# MCU103A_XDS110_MCU.net
KiCad netlist of a schematic drawn in Altium Designer
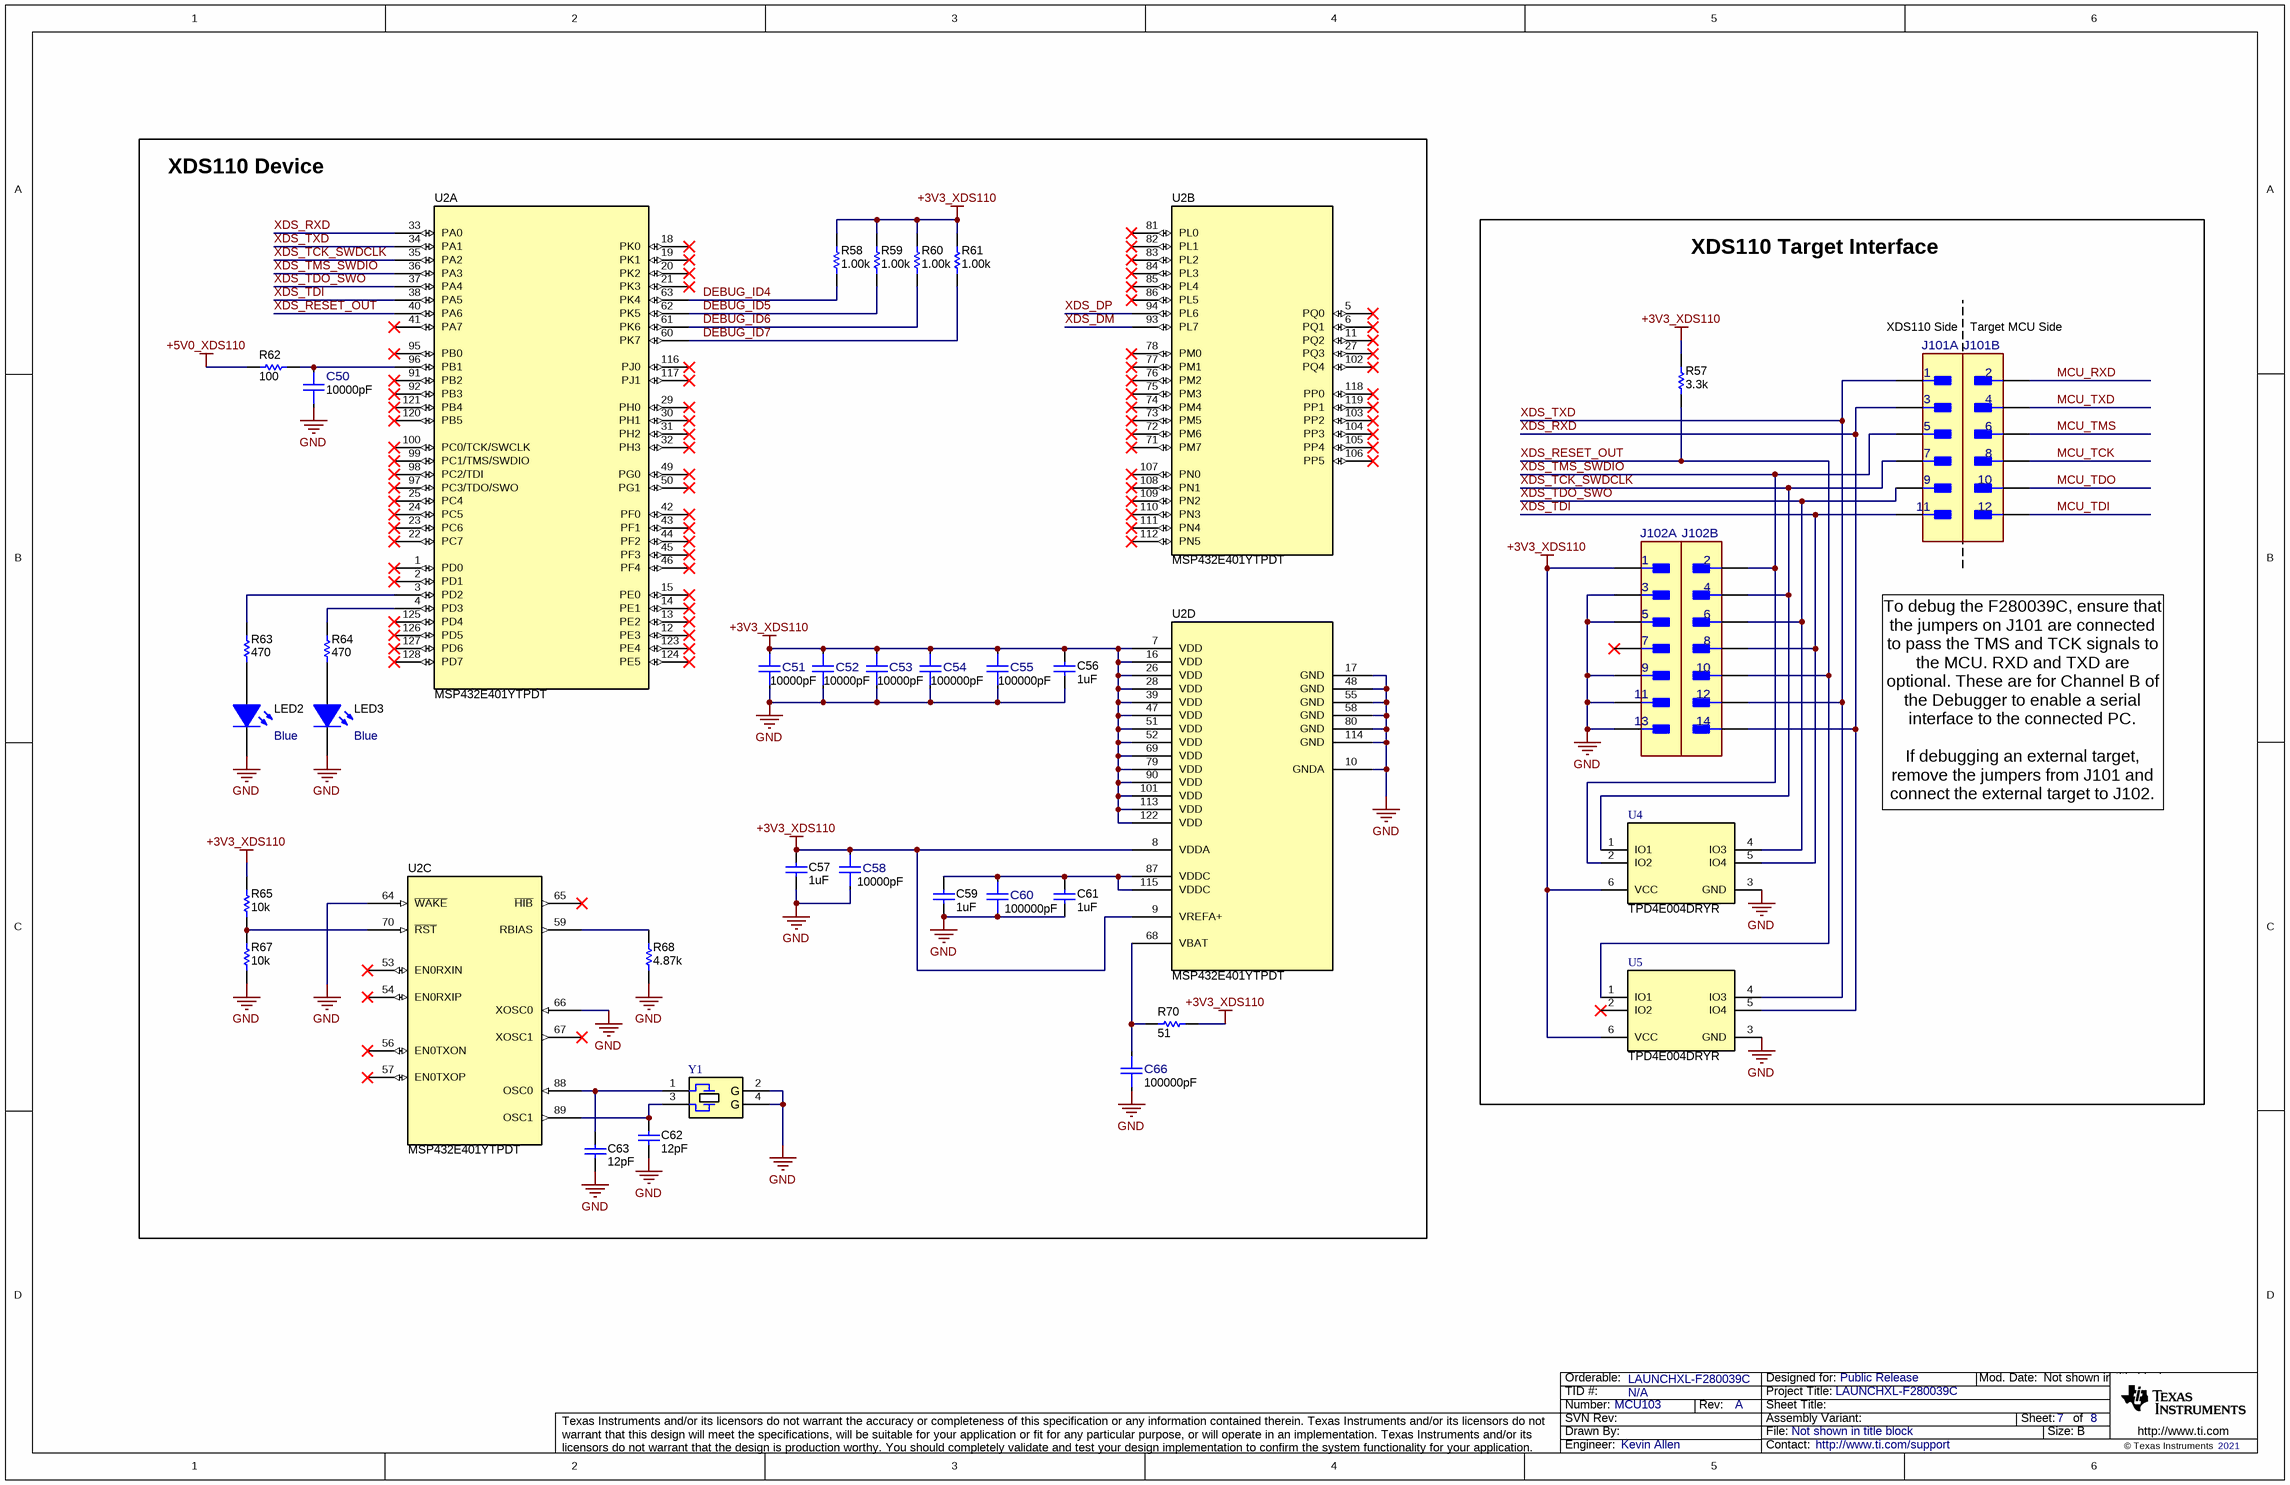
[diagram p0: MCU103A_XDS110_MCU.SchDoc]

(export (version "E")
  (design (tool "Eeschema 10.0.6"))
  (components
    (comp (ref "C50")
      (value "885012205050")
      (footprint "FP-885012205050_0402-MFG")
      (description "10000pF ±10% 25V Ceramic Capacitor X7R 0402 (1005 Metric)")
      (fields
        (field (name "MANUFACTURER") "Wurth Electronics")
        (field (name "VALUEDISPLAYED") "10000pF")
        (field (name "MOUSER PART NUMBER") "710-885012205050")
      )
      (libsource (lib "Altium Vault - TI") (part "SYM-885012205050"))
    )
    (comp (ref "C51")
      (value "885012205050")
      (footprint "FP-885012205050_0402-MFG")
      (description "10000pF ±10% 25V Ceramic Capacitor X7R 0402 (1005 Metric)")
      (fields
        (field (name "MANUFACTURER") "Wurth Electronics")
        (field (name "VALUEDISPLAYED") "10000pF")
        (field (name "MOUSER PART NUMBER") "710-885012205050")
      )
      (libsource (lib "Altium Vault - TI") (part "SYM-885012205050"))
    )
    (comp (ref "C52")
      (value "885012205050")
      (footprint "FP-885012205050_0402-MFG")
      (description "10000pF ±10% 25V Ceramic Capacitor X7R 0402 (1005 Metric)")
      (fields
        (field (name "MANUFACTURER") "Wurth Electronics")
        (field (name "VALUEDISPLAYED") "10000pF")
        (field (name "MOUSER PART NUMBER") "710-885012205050")
      )
      (libsource (lib "Altium Vault - TI") (part "SYM-885012205050"))
    )
    (comp (ref "C53")
      (value "885012205050")
      (footprint "FP-885012205050_0402-MFG")
      (description "10000pF ±10% 25V Ceramic Capacitor X7R 0402 (1005 Metric)")
      (fields
        (field (name "MANUFACTURER") "Wurth Electronics")
        (field (name "VALUEDISPLAYED") "10000pF")
        (field (name "MOUSER PART NUMBER") "710-885012205050")
      )
      (libsource (lib "Altium Vault - TI") (part "SYM-885012205050"))
    )
    (comp (ref "C54")
      (value "885012205018")
      (footprint "FP-885012205018_0402-MFG")
      (description "0.1µF ±10% 10V Ceramic Capacitor X7R 0402 (1005 Metric)")
      (fields
        (field (name "MANUFACTURER") "Wurth Electronics")
        (field (name "MOUSER PART NUMBER") "710-885012205018")
        (field (name "VALUEDISPLAYED") "100000pF")
      )
      (libsource (lib "Altium Vault - TI") (part "SYM-885012205018"))
    )
    (comp (ref "C55")
      (value "885012205018")
      (footprint "FP-885012205018_0402-MFG")
      (description "0.1µF ±10% 10V Ceramic Capacitor X7R 0402 (1005 Metric)")
      (fields
        (field (name "MANUFACTURER") "Wurth Electronics")
        (field (name "MOUSER PART NUMBER") "710-885012205018")
        (field (name "VALUEDISPLAYED") "100000pF")
      )
      (libsource (lib "Altium Vault - TI") (part "SYM-885012205018"))
    )
    (comp (ref "C56")
      (value "885012105012")
      (footprint "0402")
      (description "CAP, CERM, 1 uF, 10 V,+/- 20%, X5R, 0402")
      (fields
        (field (name "VALUEDISPLAYED") "1uF")
        (field (name "MANUFACTURER") "Wurth Elektronik")
        (field (name "PUBLISHER") "Texas Instruments")
      )
      (libsource (lib "Altium Vault - TI") (part "Capacitor"))
    )
    (comp (ref "C57")
      (value "885012105012")
      (footprint "0402")
      (description "CAP, CERM, 1 uF, 10 V,+/- 20%, X5R, 0402")
      (fields
        (field (name "VALUEDISPLAYED") "1uF")
        (field (name "MANUFACTURER") "Wurth Elektronik")
        (field (name "PUBLISHER") "Texas Instruments")
      )
      (libsource (lib "Altium Vault - TI") (part "Capacitor"))
    )
    (comp (ref "C58")
      (value "885012205050")
      (footprint "FP-885012205050_0402-MFG")
      (description "10000pF ±10% 25V Ceramic Capacitor X7R 0402 (1005 Metric)")
      (fields
        (field (name "MANUFACTURER") "Wurth Electronics")
        (field (name "VALUEDISPLAYED") "10000pF")
        (field (name "MOUSER PART NUMBER") "710-885012205050")
      )
      (libsource (lib "Altium Vault - TI") (part "SYM-885012205050"))
    )
    (comp (ref "C59")
      (value "885012105012")
      (footprint "0402")
      (description "CAP, CERM, 1 uF, 10 V,+/- 20%, X5R, 0402")
      (fields
        (field (name "VALUEDISPLAYED") "1uF")
        (field (name "MANUFACTURER") "Wurth Elektronik")
        (field (name "PUBLISHER") "Texas Instruments")
      )
      (libsource (lib "Altium Vault - TI") (part "Capacitor"))
    )
    (comp (ref "C60")
      (value "885012205018")
      (footprint "FP-885012205018_0402-MFG")
      (description "0.1µF ±10% 10V Ceramic Capacitor X7R 0402 (1005 Metric)")
      (fields
        (field (name "MANUFACTURER") "Wurth Electronics")
        (field (name "MOUSER PART NUMBER") "710-885012205018")
        (field (name "VALUEDISPLAYED") "100000pF")
      )
      (libsource (lib "Altium Vault - TI") (part "SYM-885012205018"))
    )
    (comp (ref "C61")
      (value "885012105012")
      (footprint "0402")
      (description "CAP, CERM, 1 uF, 10 V,+/- 20%, X5R, 0402")
      (fields
        (field (name "VALUEDISPLAYED") "1uF")
        (field (name "MANUFACTURER") "Wurth Elektronik")
        (field (name "PUBLISHER") "Texas Instruments")
      )
      (libsource (lib "Altium Vault - TI") (part "Capacitor"))
    )
    (comp (ref "C62")
      (value "GRM1555C1H120JA01D")
      (footprint "0402")
      (description "CAP, CERM, 12 pF, 50 V, +/- 5%, C0G/NP0, 0402")
      (fields
        (field (name "MANUFACTURER") "MuRata")
        (field (name "VALUEDISPLAYED") "12pF")
        (field (name "PUBLISHER") "Texas Instruments")
      )
      (libsource (lib "Altium Vault - TI") (part "Capacitor"))
    )
    (comp (ref "C63")
      (value "GRM1555C1H120JA01D")
      (footprint "0402")
      (description "CAP, CERM, 12 pF, 50 V, +/- 5%, C0G/NP0, 0402")
      (fields
        (field (name "MANUFACTURER") "MuRata")
        (field (name "VALUEDISPLAYED") "12pF")
        (field (name "PUBLISHER") "Texas Instruments")
      )
      (libsource (lib "Altium Vault - TI") (part "Capacitor"))
    )
    (comp (ref "C66")
      (value "885012205018")
      (footprint "FP-885012205018_0402-MFG")
      (description "0.1µF ±10% 10V Ceramic Capacitor X7R 0402 (1005 Metric)")
      (fields
        (field (name "MANUFACTURER") "Wurth Electronics")
        (field (name "MOUSER PART NUMBER") "710-885012205018")
        (field (name "VALUEDISPLAYED") "100000pF")
      )
      (libsource (lib "Altium Vault - TI") (part "SYM-885012205018"))
    )
    (comp (ref "J101")
      (value "61301221121")
      (footprint "FP-61301221121_HDR12-MFG")
      (description "THT Vertical Pin Header WR-PHD, Pitch 2.54 mm, Dual Row, 12 pins")
      (fields
        (field (name "MOUSER PART NUMBER") "710-61301221121")
        (field (name "MANUFACTURER") "Wurth Electronics")
      )
      (libsource (lib "") (part "SYM-61301221121_1"))
    )
    (comp (ref "J102")
      (value "FTSH-107-01-F-DV-K")
      (footprint "FP-FTSH-107-01-F-DV-K_HDR14-MFG")
      (description "Connector, Header, Dual Row, 14 pin, .05\" pitch/row spacing, Male, Shrouded, Keyed, IDC, SMT")
      (fields
        (field (name "MOUSER PART NUMBER") "200-FTSH10701FDVK")
        (field (name "OCTOPART PART NUMBER") "b9dd70752dfc661a")
      )
      (libsource (lib "") (part "SYM-FTSH-107-01-F-DV-K_1"))
    )
    (comp (ref "LED2")
      (value "Blue")
      (footprint "LTST-C170TBKT_Blue")
      (description "LED, Blue, SMD")
      (fields (field (name "PARTNUMBER") "LTST-C170TBKT") (field (name "MANUFACTURER") "Lite-On"))
      (libsource (lib "Altium Vault - TI") (part "LED"))
    )
    (comp (ref "LED3")
      (value "Blue")
      (footprint "LTST-C170TBKT_Blue")
      (description "LED, Blue, SMD")
      (fields (field (name "PARTNUMBER") "LTST-C170TBKT") (field (name "MANUFACTURER") "Lite-On"))
      (libsource (lib "Altium Vault - TI") (part "LED"))
    )
    (comp (ref "R57")
      (value "CRCW04023K30JNED")
      (footprint "0402")
      (description "RES, 3.3 k, 5%, 0.063 W, AEC-Q200 Grade 0, 0402")
      (fields (field (name "VALUEDISPLAYED") "3.3k") (field (name "MANUFACTURER") "Vishay-Dale"))
      (libsource (lib "Altium Vault - TI") (part "Resistor"))
    )
    (comp (ref "R58")
      (value "CRCW04021K00FKED")
      (footprint "0402")
      (description "RES, 1.00 k, 1%, 0.063 W, AEC-Q200 Grade 0, 0402")
      (fields (field (name "MANUFACTURER") "Vishay-Dale") (field (name "VALUEDISPLAYED") "1.00k"))
      (libsource (lib "Altium Vault - TI") (part "Resistor"))
    )
    (comp (ref "R59")
      (value "CRCW04021K00FKED")
      (footprint "0402")
      (description "RES, 1.00 k, 1%, 0.063 W, AEC-Q200 Grade 0, 0402")
      (fields (field (name "MANUFACTURER") "Vishay-Dale") (field (name "VALUEDISPLAYED") "1.00k"))
      (libsource (lib "Altium Vault - TI") (part "Resistor"))
    )
    (comp (ref "R60")
      (value "CRCW04021K00FKED")
      (footprint "0402")
      (description "RES, 1.00 k, 1%, 0.063 W, AEC-Q200 Grade 0, 0402")
      (fields (field (name "MANUFACTURER") "Vishay-Dale") (field (name "VALUEDISPLAYED") "1.00k"))
      (libsource (lib "Altium Vault - TI") (part "Resistor"))
    )
    (comp (ref "R61")
      (value "CRCW04021K00FKED")
      (footprint "0402")
      (description "RES, 1.00 k, 1%, 0.063 W, AEC-Q200 Grade 0, 0402")
      (fields (field (name "MANUFACTURER") "Vishay-Dale") (field (name "VALUEDISPLAYED") "1.00k"))
      (libsource (lib "Altium Vault - TI") (part "Resistor"))
    )
    (comp (ref "R62")
      (value "CRCW0402100RJNED")
      (footprint "0402")
      (description "RES, 100, 5%, 0.063 W, AEC-Q200 Grade 0, 0402")
      (fields (field (name "VALUEDISPLAYED") "100") (field (name "MANUFACTURER") "Vishay-Dale"))
      (libsource (lib "Altium Vault - TI") (part "Resistor"))
    )
    (comp (ref "R63")
      (value "RC0402FR-07470RL")
      (footprint "0402")
      (description "RES, 470, 1%, 0.063 W, 0402")
      (fields
        (field (name "MANUFACTURER") "Yageo America")
        (field (name "VALUEDISPLAYED") "470")
        (field (name "PUBLISHER") "Texas Instruments")
      )
      (libsource (lib "Altium Vault - TI") (part "Resistor"))
    )
    (comp (ref "R64")
      (value "RC0402FR-07470RL")
      (footprint "0402")
      (description "RES, 470, 1%, 0.063 W, 0402")
      (fields
        (field (name "MANUFACTURER") "Yageo America")
        (field (name "VALUEDISPLAYED") "470")
        (field (name "PUBLISHER") "Texas Instruments")
      )
      (libsource (lib "Altium Vault - TI") (part "Resistor"))
    )
    (comp (ref "R65")
      (value "CRCW040210K0JNED")
      (footprint "0402")
      (description "RES, 10 k, 5%, 0.063 W, AEC-Q200 Grade 0, 0402")
      (fields (field (name "VALUEDISPLAYED") "10k") (field (name "MANUFACTURER") "Vishay-Dale"))
      (libsource (lib "Altium Vault - TI") (part "Resistor"))
    )
    (comp (ref "R67")
      (value "CRCW040210K0JNED")
      (footprint "0402")
      (description "RES, 10 k, 5%, 0.063 W, AEC-Q200 Grade 0, 0402")
      (fields (field (name "VALUEDISPLAYED") "10k") (field (name "MANUFACTURER") "Vishay-Dale"))
      (libsource (lib "Altium Vault - TI") (part "Resistor"))
    )
    (comp (ref "R68")
      (value "CRCW04024K87FKED")
      (footprint "0402")
      (description "RES, 4.87 k, 1%, 0.063 W, AEC-Q200 Grade 0, 0402")
      (fields (field (name "VALUEDISPLAYED") "4.87k") (field (name "MANUFACTURER") "Vishay-Dale"))
      (libsource (lib "Altium Vault - TI") (part "Resistor"))
    )
    (comp (ref "R70")
      (value "CRCW040251R0JNED")
      (footprint "0402")
      (description "RES, 51, 5%, 0.063 W, AEC-Q200 Grade 0, 0402")
      (fields (field (name "VALUEDISPLAYED") "51") (field (name "MANUFACTURER") "Vishay-Dale"))
      (libsource (lib "Altium Vault - TI") (part "Resistor"))
    )
    (comp (ref "U2")
      (value "MSP432E401YTPDT")
      (footprint "PDT0128A")
      (description "MSP432E401YTPDT, PDT0128A (TQFP-128)")
      (fields
        (field (name "ALTERNATE PARTNUMBER") "MSP432E401YTPDTR")
        (field (name "MANUFACTURER") "Texas Instruments")
        (field (name "PARTNUMBER") "MSP432E401YTPDT")
      )
      (libsource (lib "Altium Vault - TI") (part "MSP432E401YTPDT"))
    )
    (comp (ref "U4")
      (value "TPD4E004DRYR")
      (footprint "DRY0006A")
      (description "4-Channel ESD Protection Array for High-Speed Data Interfaces, DRY0006A (USON-6)")
      (fields (field (name "MANUFACTURER") "Texas Instruments") (field (name "PARTNUMBER") "TPD4E004DRYR"))
      (libsource (lib "Altium Vault - TI") (part "TI-TPD4E004-SON_DRY-6"))
    )
    (comp (ref "U5")
      (value "TPD4E004DRYR")
      (footprint "DRY0006A")
      (description "4-Channel ESD Protection Array for High-Speed Data Interfaces, DRY0006A (USON-6)")
      (fields (field (name "MANUFACTURER") "Texas Instruments") (field (name "PARTNUMBER") "TPD4E004DRYR"))
      (libsource (lib "Altium Vault - TI") (part "TI-TPD4E004-SON_DRY-6"))
    )
    (comp (ref "Y1")
      (value "NX3225GA-16.000M-STD-CRG-1")
      (footprint "NDK_NX3225GA")
      (description "Crystal, 16 MHz, 8pF, SMD")
      (fields (field (name "MANUFACTURER") "NDK"))
      (libsource (lib "Altium Vault - TI") (part "XTAL_4P_13_G24"))
    )
  )
  (nets
    (net (code "1") (name "+3V3_XDS110") (class "Default")
      (node (ref "C51") (pin "2") (pinfunction "2_2") (pintype "passive"))
      (node (ref "C52") (pin "2") (pinfunction "2_2") (pintype "passive"))
      (node (ref "C53") (pin "2") (pinfunction "2_2") (pintype "passive"))
      (node (ref "C54") (pin "2") (pinfunction "2_2") (pintype "passive"))
      (node (ref "C55") (pin "2") (pinfunction "2_2") (pintype "passive"))
      (node (ref "C56") (pin "1") (pinfunction "1_1") (pintype "passive"))
      (node (ref "C57") (pin "1") (pinfunction "1_1") (pintype "passive"))
      (node (ref "C58") (pin "2") (pinfunction "2_2") (pintype "passive"))
      (node (ref "J102") (pin "1") (pinfunction "1_1") (pintype "passive"))
      (node (ref "R57") (pin "2") (pinfunction "2_2") (pintype "passive"))
      (node (ref "R58") (pin "2") (pinfunction "2_2") (pintype "passive"))
      (node (ref "R59") (pin "2") (pinfunction "2_2") (pintype "passive"))
      (node (ref "R60") (pin "2") (pinfunction "2_2") (pintype "passive"))
      (node (ref "R61") (pin "2") (pinfunction "2_2") (pintype "passive"))
      (node (ref "R65") (pin "2") (pinfunction "2_2") (pintype "passive"))
      (node (ref "R70") (pin "2") (pinfunction "2_2") (pintype "passive"))
      (node (ref "U2") (pin "101") (pinfunction "VDD_101") (pintype "power_in"))
      (node (ref "U2") (pin "113") (pinfunction "VDD_113") (pintype "power_in"))
      (node (ref "U2") (pin "122") (pinfunction "VDD_122") (pintype "power_in"))
      (node (ref "U2") (pin "16") (pinfunction "VDD_16") (pintype "power_in"))
      (node (ref "U2") (pin "26") (pinfunction "VDD_26") (pintype "power_in"))
      (node (ref "U2") (pin "28") (pinfunction "VDD_28") (pintype "power_in"))
      (node (ref "U2") (pin "39") (pinfunction "VDD_39") (pintype "power_in"))
      (node (ref "U2") (pin "47") (pinfunction "VDD_47") (pintype "power_in"))
      (node (ref "U2") (pin "51") (pinfunction "VDD_51") (pintype "power_in"))
      (node (ref "U2") (pin "52") (pinfunction "VDD_52") (pintype "power_in"))
      (node (ref "U2") (pin "69") (pinfunction "VDD_69") (pintype "power_in"))
      (node (ref "U2") (pin "7") (pinfunction "VDD_7") (pintype "power_in"))
      (node (ref "U2") (pin "79") (pinfunction "VDD_79") (pintype "power_in"))
      (node (ref "U2") (pin "8") (pinfunction "VDDA_8") (pintype "power_in"))
      (node (ref "U2") (pin "9") (pinfunction "VREFA+_9") (pintype "power_in"))
      (node (ref "U2") (pin "90") (pinfunction "VDD_90") (pintype "power_in"))
      (node (ref "U4") (pin "6") (pinfunction "VCC_6") (pintype "power_in"))
      (node (ref "U5") (pin "6") (pinfunction "VCC_6") (pintype "power_in"))
    )
    (net (code "2") (name "+5V0_XDS110") (class "Default")
      (node (ref "R62") (pin "1") (pinfunction "1_1") (pintype "passive"))
    )
    (net (code "3") (name "/DEBUG_ID4") (class "Default")
      (node (ref "R58") (pin "1") (pinfunction "1_1") (pintype "passive"))
      (node (ref "U2") (pin "63") (pinfunction "PK4_63") (pintype "bidirectional"))
    )
    (net (code "4") (name "/DEBUG_ID5") (class "Default")
      (node (ref "R59") (pin "1") (pinfunction "1_1") (pintype "passive"))
      (node (ref "U2") (pin "62") (pinfunction "PK5_62") (pintype "bidirectional"))
    )
    (net (code "5") (name "/DEBUG_ID6") (class "Default")
      (node (ref "R60") (pin "1") (pinfunction "1_1") (pintype "passive"))
      (node (ref "U2") (pin "61") (pinfunction "PK6_61") (pintype "bidirectional"))
    )
    (net (code "6") (name "/DEBUG_ID7") (class "Default")
      (node (ref "R61") (pin "1") (pinfunction "1_1") (pintype "passive"))
      (node (ref "U2") (pin "60") (pinfunction "PK7_60") (pintype "bidirectional"))
    )
    (net (code "7") (name "/MCU_RXD") (class "Default")
      (node (ref "J101") (pin "2") (pinfunction "2_2") (pintype "passive"))
    )
    (net (code "8") (name "/MCU_TCK") (class "Default")
      (node (ref "J101") (pin "8") (pinfunction "8_8") (pintype "passive"))
    )
    (net (code "9") (name "/MCU_TDI") (class "Default")
      (node (ref "J101") (pin "12") (pinfunction "12_12") (pintype "passive"))
    )
    (net (code "10") (name "/MCU_TDO") (class "Default")
      (node (ref "J101") (pin "10") (pinfunction "10_10") (pintype "passive"))
    )
    (net (code "11") (name "/MCU_TMS") (class "Default")
      (node (ref "J101") (pin "6") (pinfunction "6_6") (pintype "passive"))
    )
    (net (code "12") (name "/MCU_TXD") (class "Default")
      (node (ref "J101") (pin "4") (pinfunction "4_4") (pintype "passive"))
    )
    (net (code "13") (name "/XDS_DM") (class "Default")
      (node (ref "U2") (pin "93") (pinfunction "PL7_93") (pintype "bidirectional"))
    )
    (net (code "14") (name "/XDS_DP") (class "Default")
      (node (ref "U2") (pin "94") (pinfunction "PL6_94") (pintype "bidirectional"))
    )
    (net (code "15") (name "/XDS_RESET_OUT") (class "Default")
      (node (ref "J102") (pin "10") (pinfunction "10_10") (pintype "passive"))
      (node (ref "R57") (pin "1") (pinfunction "1_1") (pintype "passive"))
      (node (ref "U2") (pin "40") (pinfunction "PA6_40") (pintype "bidirectional"))
      (node (ref "U5") (pin "1") (pinfunction "IO1_1") (pintype "passive"))
    )
    (net (code "16") (name "/XDS_RXD") (class "Default")
      (node (ref "J101") (pin "3") (pinfunction "3_3") (pintype "passive"))
      (node (ref "J102") (pin "14") (pinfunction "14_14") (pintype "passive"))
      (node (ref "U2") (pin "33") (pinfunction "PA0_33") (pintype "bidirectional"))
      (node (ref "U5") (pin "5") (pinfunction "IO4_5") (pintype "passive"))
    )
    (net (code "17") (name "/XDS_TCK_SWDCLK") (class "Default")
      (node (ref "J101") (pin "7") (pinfunction "7_7") (pintype "passive"))
      (node (ref "J102") (pin "4") (pinfunction "4_4") (pintype "passive"))
      (node (ref "U2") (pin "35") (pinfunction "PA2_35") (pintype "bidirectional"))
      (node (ref "U4") (pin "1") (pinfunction "IO1_1") (pintype "passive"))
    )
    (net (code "18") (name "/XDS_TDI") (class "Default")
      (node (ref "J101") (pin "11") (pinfunction "11_11") (pintype "passive"))
      (node (ref "J102") (pin "8") (pinfunction "8_8") (pintype "passive"))
      (node (ref "U2") (pin "38") (pinfunction "PA5_38") (pintype "bidirectional"))
      (node (ref "U4") (pin "5") (pinfunction "IO4_5") (pintype "passive"))
    )
    (net (code "19") (name "/XDS_TDO_SWO") (class "Default")
      (node (ref "J101") (pin "9") (pinfunction "9_9") (pintype "passive"))
      (node (ref "J102") (pin "6") (pinfunction "6_6") (pintype "passive"))
      (node (ref "U2") (pin "37") (pinfunction "PA4_37") (pintype "bidirectional"))
      (node (ref "U4") (pin "4") (pinfunction "IO3_4") (pintype "passive"))
    )
    (net (code "20") (name "/XDS_TMS_SWDIO") (class "Default")
      (node (ref "J101") (pin "5") (pinfunction "5_5") (pintype "passive"))
      (node (ref "J102") (pin "2") (pinfunction "2_2") (pintype "passive"))
      (node (ref "U2") (pin "36") (pinfunction "PA3_36") (pintype "bidirectional"))
      (node (ref "U4") (pin "2") (pinfunction "IO2_2") (pintype "passive"))
    )
    (net (code "21") (name "/XDS_TXD") (class "Default")
      (node (ref "J101") (pin "1") (pinfunction "1_1") (pintype "passive"))
      (node (ref "J102") (pin "12") (pinfunction "12_12") (pintype "passive"))
      (node (ref "U2") (pin "34") (pinfunction "PA1_34") (pintype "bidirectional"))
      (node (ref "U5") (pin "4") (pinfunction "IO3_4") (pintype "passive"))
    )
    (net (code "22") (name "GND") (class "Default")
      (node (ref "C50") (pin "1") (pinfunction "1_1") (pintype "passive"))
      (node (ref "C51") (pin "1") (pinfunction "1_1") (pintype "passive"))
      (node (ref "C52") (pin "1") (pinfunction "1_1") (pintype "passive"))
      (node (ref "C53") (pin "1") (pinfunction "1_1") (pintype "passive"))
      (node (ref "C54") (pin "1") (pinfunction "1_1") (pintype "passive"))
      (node (ref "C55") (pin "1") (pinfunction "1_1") (pintype "passive"))
      (node (ref "C56") (pin "2") (pinfunction "2_2") (pintype "passive"))
      (node (ref "C57") (pin "2") (pinfunction "2_2") (pintype "passive"))
      (node (ref "C58") (pin "1") (pinfunction "1_1") (pintype "passive"))
      (node (ref "C59") (pin "2") (pinfunction "2_2") (pintype "passive"))
      (node (ref "C60") (pin "1") (pinfunction "1_1") (pintype "passive"))
      (node (ref "C61") (pin "2") (pinfunction "2_2") (pintype "passive"))
      (node (ref "C62") (pin "2") (pinfunction "2_2") (pintype "passive"))
      (node (ref "C63") (pin "2") (pinfunction "2_2") (pintype "passive"))
      (node (ref "C66") (pin "1") (pinfunction "1_1") (pintype "passive"))
      (node (ref "J102") (pin "11") (pinfunction "11_11") (pintype "passive"))
      (node (ref "J102") (pin "13") (pinfunction "13_13") (pintype "passive"))
      (node (ref "J102") (pin "3") (pinfunction "3_3") (pintype "passive"))
      (node (ref "J102") (pin "5") (pinfunction "5_5") (pintype "passive"))
      (node (ref "J102") (pin "9") (pinfunction "9_9") (pintype "passive"))
      (node (ref "LED2") (pin "2") (pinfunction "K_2") (pintype "passive"))
      (node (ref "LED3") (pin "2") (pinfunction "K_2") (pintype "passive"))
      (node (ref "R67") (pin "1") (pinfunction "1_1") (pintype "passive"))
      (node (ref "R68") (pin "1") (pinfunction "1_1") (pintype "passive"))
      (node (ref "U2") (pin "10") (pinfunction "GNDA_10") (pintype "power_in"))
      (node (ref "U2") (pin "114") (pinfunction "GND_114") (pintype "power_in"))
      (node (ref "U2") (pin "17") (pinfunction "GND_17") (pintype "power_in"))
      (node (ref "U2") (pin "48") (pinfunction "GND_48") (pintype "power_in"))
      (node (ref "U2") (pin "55") (pinfunction "GND_55") (pintype "power_in"))
      (node (ref "U2") (pin "58") (pinfunction "GND_58") (pintype "power_in"))
      (node (ref "U2") (pin "64") (pinfunction "WAKE_64") (pintype "input"))
      (node (ref "U2") (pin "66") (pinfunction "XOSC0_66") (pintype "input"))
      (node (ref "U2") (pin "80") (pinfunction "GND_80") (pintype "power_in"))
      (node (ref "U4") (pin "3") (pinfunction "GND_3") (pintype "power_in"))
      (node (ref "U5") (pin "3") (pinfunction "GND_3") (pintype "power_in"))
      (node (ref "Y1") (pin "2") (pinfunction "GND_2") (pintype "power_in"))
      (node (ref "Y1") (pin "4") (pinfunction "GND_4") (pintype "power_in"))
    )
    (net (code "23") (name "Net-(C59-Pad1)") (class "Default")
      (node (ref "C59") (pin "1") (pinfunction "1_1") (pintype "passive"))
      (node (ref "C60") (pin "2") (pinfunction "2_2") (pintype "passive"))
      (node (ref "C61") (pin "1") (pinfunction "1_1") (pintype "passive"))
      (node (ref "U2") (pin "115") (pinfunction "VDDC_115") (pintype "power_in"))
      (node (ref "U2") (pin "87") (pinfunction "VDDC_87") (pintype "power_in"))
    )
    (net (code "24") (name "Net-(LED2-A)") (class "Default")
      (node (ref "LED2") (pin "1") (pinfunction "A_1") (pintype "passive"))
      (node (ref "R63") (pin "1") (pinfunction "1_1") (pintype "passive"))
    )
    (net (code "25") (name "Net-(LED3-A)") (class "Default")
      (node (ref "LED3") (pin "1") (pinfunction "A_1") (pintype "passive"))
      (node (ref "R64") (pin "1") (pinfunction "1_1") (pintype "passive"))
    )
    (net (code "26") (name "Net-(U2A-PB1)") (class "Default")
      (node (ref "C50") (pin "2") (pinfunction "2_2") (pintype "passive"))
      (node (ref "R62") (pin "2") (pinfunction "2_2") (pintype "passive"))
      (node (ref "U2") (pin "96") (pinfunction "PB1_96") (pintype "bidirectional"))
    )
    (net (code "27") (name "Net-(U2A-PD2)") (class "Default")
      (node (ref "R63") (pin "2") (pinfunction "2_2") (pintype "passive"))
      (node (ref "U2") (pin "3") (pinfunction "PD2_3") (pintype "bidirectional"))
    )
    (net (code "28") (name "Net-(U2A-PD3)") (class "Default")
      (node (ref "R64") (pin "2") (pinfunction "2_2") (pintype "passive"))
      (node (ref "U2") (pin "4") (pinfunction "PD3_4") (pintype "bidirectional"))
    )
    (net (code "29") (name "Net-(U2C-OSC0)") (class "Default")
      (node (ref "C63") (pin "1") (pinfunction "1_1") (pintype "passive"))
      (node (ref "U2") (pin "88") (pinfunction "OSC0_88") (pintype "input"))
      (node (ref "Y1") (pin "1") (pinfunction "1_1") (pintype "passive"))
    )
    (net (code "30") (name "Net-(U2C-OSC1)") (class "Default")
      (node (ref "C62") (pin "1") (pinfunction "1_1") (pintype "passive"))
      (node (ref "U2") (pin "89") (pinfunction "OSC1_89") (pintype "output"))
      (node (ref "Y1") (pin "3") (pinfunction "3_3") (pintype "passive"))
    )
    (net (code "31") (name "Net-(U2C-RBIAS)") (class "Default")
      (node (ref "R68") (pin "2") (pinfunction "2_2") (pintype "passive"))
      (node (ref "U2") (pin "59") (pinfunction "RBIAS_59") (pintype "output"))
    )
    (net (code "32") (name "Net-(U2C-RST)") (class "Default")
      (node (ref "R65") (pin "1") (pinfunction "1_1") (pintype "passive"))
      (node (ref "R67") (pin "2") (pinfunction "2_2") (pintype "passive"))
      (node (ref "U2") (pin "70") (pinfunction "RST_70") (pintype "input"))
    )
    (net (code "33") (name "Net-(U2D-VBAT)") (class "Default")
      (node (ref "C66") (pin "2") (pinfunction "2_2") (pintype "passive"))
      (node (ref "R70") (pin "1") (pinfunction "1_1") (pintype "passive"))
      (node (ref "U2") (pin "68") (pinfunction "VBAT_68") (pintype "power_in"))
    )
    (net (code "34") (name "unconnected-(J102-Pad7)") (class "Default")
      (node (ref "J102") (pin "7") (pinfunction "7_7") (pintype "passive+no_connect"))
    )
    (net (code "35") (name "unconnected-(U2A-PA7-Pad41)") (class "Default")
      (node (ref "U2") (pin "41") (pinfunction "PA7_41") (pintype "bidirectional+no_connect"))
    )
    (net (code "36") (name "unconnected-(U2A-PB0-Pad95)") (class "Default")
      (node (ref "U2") (pin "95") (pinfunction "PB0_95") (pintype "bidirectional+no_connect"))
    )
    (net (code "37") (name "unconnected-(U2A-PB2-Pad91)") (class "Default")
      (node (ref "U2") (pin "91") (pinfunction "PB2_91") (pintype "bidirectional+no_connect"))
    )
    (net (code "38") (name "unconnected-(U2A-PB3-Pad92)") (class "Default")
      (node (ref "U2") (pin "92") (pinfunction "PB3_92") (pintype "bidirectional+no_connect"))
    )
    (net (code "39") (name "unconnected-(U2A-PB4-Pad121)") (class "Default")
      (node (ref "U2") (pin "121") (pinfunction "PB4_121") (pintype "bidirectional+no_connect"))
    )
    (net (code "40") (name "unconnected-(U2A-PB5-Pad120)") (class "Default")
      (node (ref "U2") (pin "120") (pinfunction "PB5_120") (pintype "bidirectional+no_connect"))
    )
    (net (code "41") (name "unconnected-(U2A-PC0{slash}TCK{slash}SWCLK-Pad100)") (class "Default")
      (node (ref "U2") (pin "100") (pinfunction "PC0/TCK/SWCLK_100") (pintype "bidirectional+no_connect"))
    )
    (net (code "42") (name "unconnected-(U2A-PC1{slash}TMS{slash}SWDIO-Pad99)") (class "Default")
      (node (ref "U2") (pin "99") (pinfunction "PC1/TMS/SWDIO_99") (pintype "bidirectional+no_connect"))
    )
    (net (code "43") (name "unconnected-(U2A-PC2{slash}TDI-Pad98)") (class "Default")
      (node (ref "U2") (pin "98") (pinfunction "PC2/TDI_98") (pintype "bidirectional+no_connect"))
    )
    (net (code "44") (name "unconnected-(U2A-PC3{slash}TDO{slash}SWO-Pad97)") (class "Default")
      (node (ref "U2") (pin "97") (pinfunction "PC3/TDO/SWO_97") (pintype "bidirectional+no_connect"))
    )
    (net (code "45") (name "unconnected-(U2A-PC4-Pad25)") (class "Default")
      (node (ref "U2") (pin "25") (pinfunction "PC4_25") (pintype "bidirectional+no_connect"))
    )
    (net (code "46") (name "unconnected-(U2A-PC5-Pad24)") (class "Default")
      (node (ref "U2") (pin "24") (pinfunction "PC5_24") (pintype "bidirectional+no_connect"))
    )
    (net (code "47") (name "unconnected-(U2A-PC6-Pad23)") (class "Default")
      (node (ref "U2") (pin "23") (pinfunction "PC6_23") (pintype "bidirectional+no_connect"))
    )
    (net (code "48") (name "unconnected-(U2A-PC7-Pad22)") (class "Default")
      (node (ref "U2") (pin "22") (pinfunction "PC7_22") (pintype "bidirectional+no_connect"))
    )
    (net (code "49") (name "unconnected-(U2A-PD0-Pad1)") (class "Default")
      (node (ref "U2") (pin "1") (pinfunction "PD0_1") (pintype "bidirectional+no_connect"))
    )
    (net (code "50") (name "unconnected-(U2A-PD1-Pad2)") (class "Default")
      (node (ref "U2") (pin "2") (pinfunction "PD1_2") (pintype "bidirectional+no_connect"))
    )
    (net (code "51") (name "unconnected-(U2A-PD4-Pad125)") (class "Default")
      (node (ref "U2") (pin "125") (pinfunction "PD4_125") (pintype "bidirectional+no_connect"))
    )
    (net (code "52") (name "unconnected-(U2A-PD5-Pad126)") (class "Default")
      (node (ref "U2") (pin "126") (pinfunction "PD5_126") (pintype "bidirectional+no_connect"))
    )
    (net (code "53") (name "unconnected-(U2A-PD6-Pad127)") (class "Default")
      (node (ref "U2") (pin "127") (pinfunction "PD6_127") (pintype "bidirectional+no_connect"))
    )
    (net (code "54") (name "unconnected-(U2A-PD7-Pad128)") (class "Default")
      (node (ref "U2") (pin "128") (pinfunction "PD7_128") (pintype "bidirectional+no_connect"))
    )
    (net (code "55") (name "unconnected-(U2A-PE0-Pad15)") (class "Default")
      (node (ref "U2") (pin "15") (pinfunction "PE0_15") (pintype "bidirectional+no_connect"))
    )
    (net (code "56") (name "unconnected-(U2A-PE1-Pad14)") (class "Default")
      (node (ref "U2") (pin "14") (pinfunction "PE1_14") (pintype "bidirectional+no_connect"))
    )
    (net (code "57") (name "unconnected-(U2A-PE2-Pad13)") (class "Default")
      (node (ref "U2") (pin "13") (pinfunction "PE2_13") (pintype "bidirectional+no_connect"))
    )
    (net (code "58") (name "unconnected-(U2A-PE3-Pad12)") (class "Default")
      (node (ref "U2") (pin "12") (pinfunction "PE3_12") (pintype "bidirectional+no_connect"))
    )
    (net (code "59") (name "unconnected-(U2A-PE4-Pad123)") (class "Default")
      (node (ref "U2") (pin "123") (pinfunction "PE4_123") (pintype "bidirectional+no_connect"))
    )
    (net (code "60") (name "unconnected-(U2A-PE5-Pad124)") (class "Default")
      (node (ref "U2") (pin "124") (pinfunction "PE5_124") (pintype "bidirectional+no_connect"))
    )
    (net (code "61") (name "unconnected-(U2A-PF0-Pad42)") (class "Default")
      (node (ref "U2") (pin "42") (pinfunction "PF0_42") (pintype "bidirectional+no_connect"))
    )
    (net (code "62") (name "unconnected-(U2A-PF1-Pad43)") (class "Default")
      (node (ref "U2") (pin "43") (pinfunction "PF1_43") (pintype "bidirectional+no_connect"))
    )
    (net (code "63") (name "unconnected-(U2A-PF2-Pad44)") (class "Default")
      (node (ref "U2") (pin "44") (pinfunction "PF2_44") (pintype "bidirectional+no_connect"))
    )
    (net (code "64") (name "unconnected-(U2A-PF3-Pad45)") (class "Default")
      (node (ref "U2") (pin "45") (pinfunction "PF3_45") (pintype "bidirectional+no_connect"))
    )
    (net (code "65") (name "unconnected-(U2A-PF4-Pad46)") (class "Default")
      (node (ref "U2") (pin "46") (pinfunction "PF4_46") (pintype "bidirectional+no_connect"))
    )
    (net (code "66") (name "unconnected-(U2A-PG0-Pad49)") (class "Default")
      (node (ref "U2") (pin "49") (pinfunction "PG0_49") (pintype "bidirectional+no_connect"))
    )
    (net (code "67") (name "unconnected-(U2A-PG1-Pad50)") (class "Default")
      (node (ref "U2") (pin "50") (pinfunction "PG1_50") (pintype "bidirectional+no_connect"))
    )
    (net (code "68") (name "unconnected-(U2A-PH0-Pad29)") (class "Default")
      (node (ref "U2") (pin "29") (pinfunction "PH0_29") (pintype "bidirectional+no_connect"))
    )
    (net (code "69") (name "unconnected-(U2A-PH1-Pad30)") (class "Default")
      (node (ref "U2") (pin "30") (pinfunction "PH1_30") (pintype "bidirectional+no_connect"))
    )
    (net (code "70") (name "unconnected-(U2A-PH2-Pad31)") (class "Default")
      (node (ref "U2") (pin "31") (pinfunction "PH2_31") (pintype "bidirectional+no_connect"))
    )
    (net (code "71") (name "unconnected-(U2A-PH3-Pad32)") (class "Default")
      (node (ref "U2") (pin "32") (pinfunction "PH3_32") (pintype "bidirectional+no_connect"))
    )
    (net (code "72") (name "unconnected-(U2A-PJ0-Pad116)") (class "Default")
      (node (ref "U2") (pin "116") (pinfunction "PJ0_116") (pintype "bidirectional+no_connect"))
    )
    (net (code "73") (name "unconnected-(U2A-PJ1-Pad117)") (class "Default")
      (node (ref "U2") (pin "117") (pinfunction "PJ1_117") (pintype "bidirectional+no_connect"))
    )
    (net (code "74") (name "unconnected-(U2A-PK0-Pad18)") (class "Default")
      (node (ref "U2") (pin "18") (pinfunction "PK0_18") (pintype "bidirectional+no_connect"))
    )
    (net (code "75") (name "unconnected-(U2A-PK1-Pad19)") (class "Default")
      (node (ref "U2") (pin "19") (pinfunction "PK1_19") (pintype "bidirectional+no_connect"))
    )
    (net (code "76") (name "unconnected-(U2A-PK2-Pad20)") (class "Default")
      (node (ref "U2") (pin "20") (pinfunction "PK2_20") (pintype "bidirectional+no_connect"))
    )
    (net (code "77") (name "unconnected-(U2A-PK3-Pad21)") (class "Default")
      (node (ref "U2") (pin "21") (pinfunction "PK3_21") (pintype "bidirectional+no_connect"))
    )
    (net (code "78") (name "unconnected-(U2B-PL0-Pad81)") (class "Default")
      (node (ref "U2") (pin "81") (pinfunction "PL0_81") (pintype "bidirectional+no_connect"))
    )
    (net (code "79") (name "unconnected-(U2B-PL1-Pad82)") (class "Default")
      (node (ref "U2") (pin "82") (pinfunction "PL1_82") (pintype "bidirectional+no_connect"))
    )
    (net (code "80") (name "unconnected-(U2B-PL2-Pad83)") (class "Default")
      (node (ref "U2") (pin "83") (pinfunction "PL2_83") (pintype "bidirectional+no_connect"))
    )
    (net (code "81") (name "unconnected-(U2B-PL3-Pad84)") (class "Default")
      (node (ref "U2") (pin "84") (pinfunction "PL3_84") (pintype "bidirectional+no_connect"))
    )
    (net (code "82") (name "unconnected-(U2B-PL4-Pad85)") (class "Default")
      (node (ref "U2") (pin "85") (pinfunction "PL4_85") (pintype "bidirectional+no_connect"))
    )
    (net (code "83") (name "unconnected-(U2B-PL5-Pad86)") (class "Default")
      (node (ref "U2") (pin "86") (pinfunction "PL5_86") (pintype "bidirectional+no_connect"))
    )
    (net (code "84") (name "unconnected-(U2B-PM0-Pad78)") (class "Default")
      (node (ref "U2") (pin "78") (pinfunction "PM0_78") (pintype "bidirectional+no_connect"))
    )
    (net (code "85") (name "unconnected-(U2B-PM1-Pad77)") (class "Default")
      (node (ref "U2") (pin "77") (pinfunction "PM1_77") (pintype "bidirectional+no_connect"))
    )
    (net (code "86") (name "unconnected-(U2B-PM2-Pad76)") (class "Default")
      (node (ref "U2") (pin "76") (pinfunction "PM2_76") (pintype "bidirectional+no_connect"))
    )
    (net (code "87") (name "unconnected-(U2B-PM3-Pad75)") (class "Default")
      (node (ref "U2") (pin "75") (pinfunction "PM3_75") (pintype "bidirectional+no_connect"))
    )
    (net (code "88") (name "unconnected-(U2B-PM4-Pad74)") (class "Default")
      (node (ref "U2") (pin "74") (pinfunction "PM4_74") (pintype "bidirectional+no_connect"))
    )
    (net (code "89") (name "unconnected-(U2B-PM5-Pad73)") (class "Default")
      (node (ref "U2") (pin "73") (pinfunction "PM5_73") (pintype "bidirectional+no_connect"))
    )
    (net (code "90") (name "unconnected-(U2B-PM6-Pad72)") (class "Default")
      (node (ref "U2") (pin "72") (pinfunction "PM6_72") (pintype "bidirectional+no_connect"))
    )
    (net (code "91") (name "unconnected-(U2B-PM7-Pad71)") (class "Default")
      (node (ref "U2") (pin "71") (pinfunction "PM7_71") (pintype "bidirectional+no_connect"))
    )
    (net (code "92") (name "unconnected-(U2B-PN0-Pad107)") (class "Default")
      (node (ref "U2") (pin "107") (pinfunction "PN0_107") (pintype "bidirectional+no_connect"))
    )
    (net (code "93") (name "unconnected-(U2B-PN1-Pad108)") (class "Default")
      (node (ref "U2") (pin "108") (pinfunction "PN1_108") (pintype "bidirectional+no_connect"))
    )
    (net (code "94") (name "unconnected-(U2B-PN2-Pad109)") (class "Default")
      (node (ref "U2") (pin "109") (pinfunction "PN2_109") (pintype "bidirectional+no_connect"))
    )
    (net (code "95") (name "unconnected-(U2B-PN3-Pad110)") (class "Default")
      (node (ref "U2") (pin "110") (pinfunction "PN3_110") (pintype "bidirectional+no_connect"))
    )
    (net (code "96") (name "unconnected-(U2B-PN4-Pad111)") (class "Default")
      (node (ref "U2") (pin "111") (pinfunction "PN4_111") (pintype "bidirectional+no_connect"))
    )
    (net (code "97") (name "unconnected-(U2B-PN5-Pad112)") (class "Default")
      (node (ref "U2") (pin "112") (pinfunction "PN5_112") (pintype "bidirectional+no_connect"))
    )
    (net (code "98") (name "unconnected-(U2B-PP0-Pad118)") (class "Default")
      (node (ref "U2") (pin "118") (pinfunction "PP0_118") (pintype "bidirectional+no_connect"))
    )
    (net (code "99") (name "unconnected-(U2B-PP1-Pad119)") (class "Default")
      (node (ref "U2") (pin "119") (pinfunction "PP1_119") (pintype "bidirectional+no_connect"))
    )
    (net (code "100") (name "unconnected-(U2B-PP2-Pad103)") (class "Default")
      (node (ref "U2") (pin "103") (pinfunction "PP2_103") (pintype "bidirectional+no_connect"))
    )
    (net (code "101") (name "unconnected-(U2B-PP3-Pad104)") (class "Default")
      (node (ref "U2") (pin "104") (pinfunction "PP3_104") (pintype "bidirectional+no_connect"))
    )
    (net (code "102") (name "unconnected-(U2B-PP4-Pad105)") (class "Default")
      (node (ref "U2") (pin "105") (pinfunction "PP4_105") (pintype "bidirectional+no_connect"))
    )
    (net (code "103") (name "unconnected-(U2B-PP5-Pad106)") (class "Default")
      (node (ref "U2") (pin "106") (pinfunction "PP5_106") (pintype "bidirectional+no_connect"))
    )
    (net (code "104") (name "unconnected-(U2B-PQ0-Pad5)") (class "Default")
      (node (ref "U2") (pin "5") (pinfunction "PQ0_5") (pintype "bidirectional+no_connect"))
    )
    (net (code "105") (name "unconnected-(U2B-PQ1-Pad6)") (class "Default")
      (node (ref "U2") (pin "6") (pinfunction "PQ1_6") (pintype "bidirectional+no_connect"))
    )
    (net (code "106") (name "unconnected-(U2B-PQ2-Pad11)") (class "Default")
      (node (ref "U2") (pin "11") (pinfunction "PQ2_11") (pintype "bidirectional+no_connect"))
    )
    (net (code "107") (name "unconnected-(U2B-PQ3-Pad27)") (class "Default")
      (node (ref "U2") (pin "27") (pinfunction "PQ3_27") (pintype "bidirectional+no_connect"))
    )
    (net (code "108") (name "unconnected-(U2B-PQ4-Pad102)") (class "Default")
      (node (ref "U2") (pin "102") (pinfunction "PQ4_102") (pintype "bidirectional+no_connect"))
    )
    (net (code "109") (name "unconnected-(U2C-EN0RXIN-Pad53)") (class "Default")
      (node (ref "U2") (pin "53") (pinfunction "EN0RXIN_53") (pintype "bidirectional+no_connect"))
    )
    (net (code "110") (name "unconnected-(U2C-EN0RXIP-Pad54)") (class "Default")
      (node (ref "U2") (pin "54") (pinfunction "EN0RXIP_54") (pintype "bidirectional+no_connect"))
    )
    (net (code "111") (name "unconnected-(U2C-EN0TXON-Pad56)") (class "Default")
      (node (ref "U2") (pin "56") (pinfunction "EN0TXON_56") (pintype "bidirectional+no_connect"))
    )
    (net (code "112") (name "unconnected-(U2C-EN0TXOP-Pad57)") (class "Default")
      (node (ref "U2") (pin "57") (pinfunction "EN0TXOP_57") (pintype "bidirectional+no_connect"))
    )
    (net (code "113") (name "unconnected-(U2C-HIB-Pad65)") (class "Default")
      (node (ref "U2") (pin "65") (pinfunction "HIB_65") (pintype "output+no_connect"))
    )
    (net (code "114") (name "unconnected-(U2C-XOSC1-Pad67)") (class "Default")
      (node (ref "U2") (pin "67") (pinfunction "XOSC1_67") (pintype "output+no_connect"))
    )
    (net (code "115") (name "unconnected-(U5-IO2-Pad2)") (class "Default")
      (node (ref "U5") (pin "2") (pinfunction "IO2_2") (pintype "passive+no_connect"))
    )
  )
)
